# CANBUS.net
KiCad netlist of a schematic drawn in Altium Designer
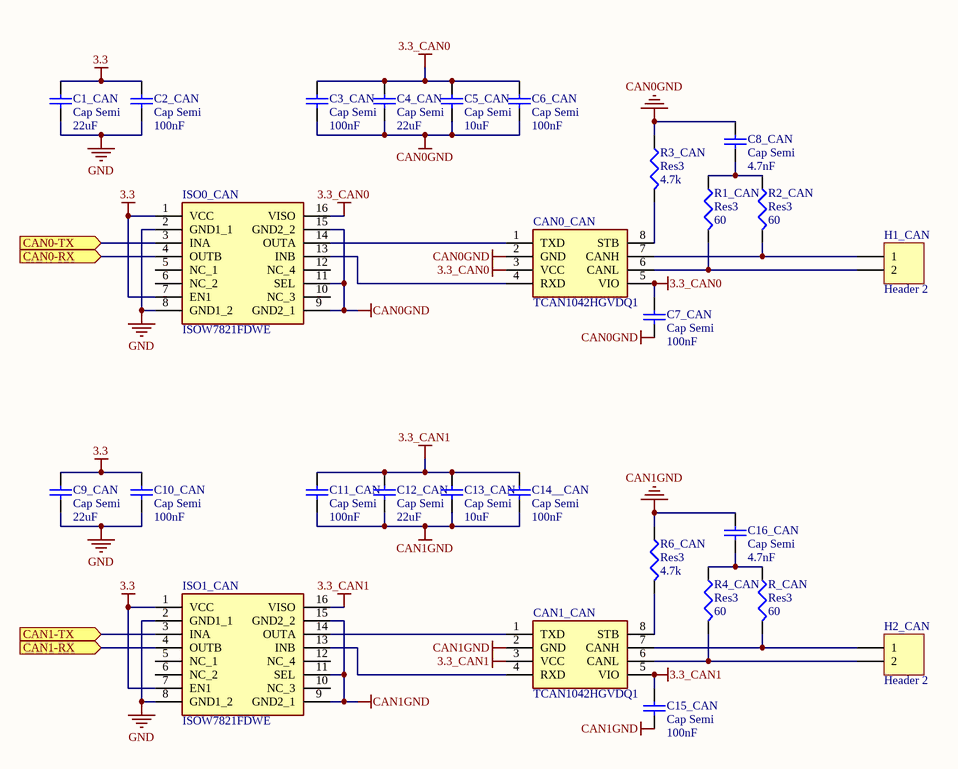
[diagram p0: CANBUS.SchDoc]

(export (version "E")
  (design (tool "Eeschema 10.0.6"))
  (components
    (comp (ref "C1_CAN")
      (value "Cap Semi")
      (footprint "1608[0603]")
      (description "Capacitor (Semiconductor SIM Model)")
      (fields (field (name "ALTIUM_VALUE") "22uF") (field (name "PUBLISHER") "Altium Limited"))
      (libsource (lib "Miscellaneous Devices") (part "Cap Semi"))
    )
    (comp (ref "C2_CAN")
      (value "Cap Semi")
      (footprint "1608[0603]")
      (description "Capacitor (Semiconductor SIM Model)")
      (fields (field (name "ALTIUM_VALUE") "100nF") (field (name "PUBLISHER") "Altium Limited"))
      (libsource (lib "Miscellaneous Devices") (part "Cap Semi"))
    )
    (comp (ref "C3_CAN")
      (value "Cap Semi")
      (footprint "1608[0603]")
      (description "Capacitor (Semiconductor SIM Model)")
      (fields (field (name "ALTIUM_VALUE") "100nF") (field (name "PUBLISHER") "Altium Limited"))
      (libsource (lib "Miscellaneous Devices") (part "Cap Semi"))
    )
    (comp (ref "C4_CAN")
      (value "Cap Semi")
      (footprint "1608[0603]")
      (description "Capacitor (Semiconductor SIM Model)")
      (fields (field (name "ALTIUM_VALUE") "22uF") (field (name "PUBLISHER") "Altium Limited"))
      (libsource (lib "Miscellaneous Devices") (part "Cap Semi"))
    )
    (comp (ref "C5_CAN")
      (value "Cap Semi")
      (footprint "1608[0603]")
      (description "Capacitor (Semiconductor SIM Model)")
      (fields (field (name "ALTIUM_VALUE") "10uF") (field (name "PUBLISHER") "Altium Limited"))
      (libsource (lib "Miscellaneous Devices") (part "Cap Semi"))
    )
    (comp (ref "C6_CAN")
      (value "Cap Semi")
      (footprint "1608[0603]")
      (description "Capacitor (Semiconductor SIM Model)")
      (fields (field (name "ALTIUM_VALUE") "100nF") (field (name "PUBLISHER") "Altium Limited"))
      (libsource (lib "Miscellaneous Devices") (part "Cap Semi"))
    )
    (comp (ref "C7_CAN")
      (value "Cap Semi")
      (footprint "1608[0603]")
      (description "Capacitor (Semiconductor SIM Model)")
      (fields (field (name "ALTIUM_VALUE") "100nF") (field (name "PUBLISHER") "Altium Limited"))
      (libsource (lib "Miscellaneous Devices") (part "Cap Semi"))
    )
    (comp (ref "C8_CAN")
      (value "Cap Semi")
      (footprint "1608[0603]")
      (description "Capacitor (Semiconductor SIM Model)")
      (fields (field (name "ALTIUM_VALUE") "4.7nF") (field (name "PUBLISHER") "Altium Limited"))
      (libsource (lib "Miscellaneous Devices") (part "Cap Semi"))
    )
    (comp (ref "C9_CAN")
      (value "Cap Semi")
      (footprint "1608[0603]")
      (description "Capacitor (Semiconductor SIM Model)")
      (fields (field (name "ALTIUM_VALUE") "22uF") (field (name "PUBLISHER") "Altium Limited"))
      (libsource (lib "Miscellaneous Devices") (part "Cap Semi"))
    )
    (comp (ref "C10_CAN")
      (value "Cap Semi")
      (footprint "1608[0603]")
      (description "Capacitor (Semiconductor SIM Model)")
      (fields (field (name "ALTIUM_VALUE") "100nF") (field (name "PUBLISHER") "Altium Limited"))
      (libsource (lib "Miscellaneous Devices") (part "Cap Semi"))
    )
    (comp (ref "C11_CAN")
      (value "Cap Semi")
      (footprint "1608[0603]")
      (description "Capacitor (Semiconductor SIM Model)")
      (fields (field (name "ALTIUM_VALUE") "100nF") (field (name "PUBLISHER") "Altium Limited"))
      (libsource (lib "Miscellaneous Devices") (part "Cap Semi"))
    )
    (comp (ref "C12_CAN")
      (value "Cap Semi")
      (footprint "1608[0603]")
      (description "Capacitor (Semiconductor SIM Model)")
      (fields (field (name "ALTIUM_VALUE") "22uF") (field (name "PUBLISHER") "Altium Limited"))
      (libsource (lib "Miscellaneous Devices") (part "Cap Semi"))
    )
    (comp (ref "C13_CAN")
      (value "Cap Semi")
      (footprint "1608[0603]")
      (description "Capacitor (Semiconductor SIM Model)")
      (fields (field (name "ALTIUM_VALUE") "10uF") (field (name "PUBLISHER") "Altium Limited"))
      (libsource (lib "Miscellaneous Devices") (part "Cap Semi"))
    )
    (comp (ref "C14__CAN")
      (value "Cap Semi")
      (footprint "1608[0603]")
      (description "Capacitor (Semiconductor SIM Model)")
      (fields (field (name "ALTIUM_VALUE") "100nF") (field (name "PUBLISHER") "Altium Limited"))
      (libsource (lib "Miscellaneous Devices") (part "Cap Semi"))
    )
    (comp (ref "C15_CAN")
      (value "Cap Semi")
      (footprint "1608[0603]")
      (description "Capacitor (Semiconductor SIM Model)")
      (fields (field (name "ALTIUM_VALUE") "100nF") (field (name "PUBLISHER") "Altium Limited"))
      (libsource (lib "Miscellaneous Devices") (part "Cap Semi"))
    )
    (comp (ref "C16_CAN")
      (value "Cap Semi")
      (footprint "1608[0603]")
      (description "Capacitor (Semiconductor SIM Model)")
      (fields (field (name "ALTIUM_VALUE") "4.7nF") (field (name "PUBLISHER") "Altium Limited"))
      (libsource (lib "Miscellaneous Devices") (part "Cap Semi"))
    )
    (comp (ref "CAN0_CAN")
      (value "TCAN1042HGVDQ1")
      (footprint "SOIC127P600X175-8N")
      (description "Integrated Circuit")
      (fields
        (field (name "MOUSER PART NUMBER") "595-TCAN1042HGVDQ1")
        (field (name "RS PART NUMBER") "1330710P")
      )
      (libsource (lib "CANBUS") (part "TCAN1042HGVDQ1"))
    )
    (comp (ref "CAN1_CAN")
      (value "TCAN1042HGVDQ1")
      (footprint "SOIC127P600X175-8N")
      (description "Integrated Circuit")
      (fields
        (field (name "MOUSER PART NUMBER") "595-TCAN1042HGVDQ1")
        (field (name "RS PART NUMBER") "1330710P")
      )
      (libsource (lib "CANBUS") (part "TCAN1042HGVDQ1"))
    )
    (comp (ref "H1_CAN")
      (value "Header 2")
      (footprint "HDR1X2")
      (description "Header, 2-Pin")
      (fields (field (name "PUBLISHER") "Altium Limited"))
      (libsource (lib "Miscellaneous Connectors") (part "Header 2"))
    )
    (comp (ref "H2_CAN")
      (value "Header 2")
      (footprint "HDR1X2")
      (description "Header, 2-Pin")
      (fields (field (name "PUBLISHER") "Altium Limited"))
      (libsource (lib "Miscellaneous Connectors") (part "Header 2"))
    )
    (comp (ref "ISO0_CAN")
      (value "ISOW7821FDWE")
      (footprint "SOIC127P1030X265-16N")
      (description "Integrated Circuit")
      (fields (field (name "MOUSER PART NUMBER") "595-ISOW7821FDWE"))
      (libsource (lib "CANBUS") (part "ISOW7821FDWE"))
    )
    (comp (ref "ISO1_CAN")
      (value "ISOW7821FDWE")
      (footprint "SOIC127P1030X265-16N")
      (description "Integrated Circuit")
      (fields (field (name "MOUSER PART NUMBER") "595-ISOW7821FDWE"))
      (libsource (lib "CANBUS") (part "ISOW7821FDWE"))
    )
    (comp (ref "R1_CAN")
      (value "Res3")
      (footprint "J1-0603")
      (description "Resistor")
      (fields (field (name "ALTIUM_VALUE") "60") (field (name "PUBLISHER") "Altium Limited"))
      (libsource (lib "Miscellaneous Devices") (part "Res3"))
    )
    (comp (ref "R2_CAN")
      (value "Res3")
      (footprint "J1-0603")
      (description "Resistor")
      (fields (field (name "ALTIUM_VALUE") "60") (field (name "PUBLISHER") "Altium Limited"))
      (libsource (lib "Miscellaneous Devices") (part "Res3"))
    )
    (comp (ref "R3_CAN")
      (value "Res3")
      (footprint "J1-0603")
      (description "Resistor")
      (fields (field (name "ALTIUM_VALUE") "4.7k") (field (name "PUBLISHER") "Altium Limited"))
      (libsource (lib "Miscellaneous Devices") (part "Res3"))
    )
    (comp (ref "R4_CAN")
      (value "Res3")
      (footprint "J1-0603")
      (description "Resistor")
      (fields (field (name "ALTIUM_VALUE") "60") (field (name "PUBLISHER") "Altium Limited"))
      (libsource (lib "Miscellaneous Devices") (part "Res3"))
    )
    (comp (ref "R6_CAN")
      (value "Res3")
      (footprint "J1-0603")
      (description "Resistor")
      (fields (field (name "ALTIUM_VALUE") "4.7k") (field (name "PUBLISHER") "Altium Limited"))
      (libsource (lib "Miscellaneous Devices") (part "Res3"))
    )
    (comp (ref "R_CAN")
      (value "Res3")
      (footprint "J1-0603")
      (description "Resistor")
      (fields (field (name "ALTIUM_VALUE") "60") (field (name "PUBLISHER") "Altium Limited"))
      (libsource (lib "Miscellaneous Devices") (part "Res3"))
    )
  )
  (nets
    (net (code "1") (name "/CAN0-RX") (class "Default")
      (node (ref "ISO0_CAN") (pin "4") (pinfunction "OUTB_4") (pintype "passive"))
    )
    (net (code "2") (name "/CAN0-TX") (class "Default")
      (node (ref "ISO0_CAN") (pin "3") (pinfunction "INA_3") (pintype "passive"))
    )
    (net (code "3") (name "/CAN1-RX") (class "Default")
      (node (ref "ISO1_CAN") (pin "4") (pinfunction "OUTB_4") (pintype "passive"))
    )
    (net (code "4") (name "/CAN1-TX") (class "Default")
      (node (ref "ISO1_CAN") (pin "3") (pinfunction "INA_3") (pintype "passive"))
    )
    (net (code "5") (name "3.3") (class "Default")
      (node (ref "C10_CAN") (pin "2") (pinfunction "2_2") (pintype "passive"))
      (node (ref "C1_CAN") (pin "2") (pinfunction "2_2") (pintype "passive"))
      (node (ref "C2_CAN") (pin "2") (pinfunction "2_2") (pintype "passive"))
      (node (ref "C9_CAN") (pin "2") (pinfunction "2_2") (pintype "passive"))
      (node (ref "ISO0_CAN") (pin "1") (pinfunction "VCC_1") (pintype "passive"))
      (node (ref "ISO0_CAN") (pin "7") (pinfunction "EN1_7") (pintype "passive"))
      (node (ref "ISO1_CAN") (pin "1") (pinfunction "VCC_1") (pintype "passive"))
      (node (ref "ISO1_CAN") (pin "7") (pinfunction "EN1_7") (pintype "passive"))
    )
    (net (code "6") (name "3.3_CAN0") (class "Default")
      (node (ref "C3_CAN") (pin "2") (pinfunction "2_2") (pintype "passive"))
      (node (ref "C4_CAN") (pin "2") (pinfunction "2_2") (pintype "passive"))
      (node (ref "C5_CAN") (pin "2") (pinfunction "2_2") (pintype "passive"))
      (node (ref "C6_CAN") (pin "2") (pinfunction "2_2") (pintype "passive"))
      (node (ref "C7_CAN") (pin "2") (pinfunction "2_2") (pintype "passive"))
      (node (ref "CAN0_CAN") (pin "3") (pinfunction "VCC_3") (pintype "power_in"))
      (node (ref "CAN0_CAN") (pin "5") (pinfunction "VIO_5") (pintype "power_in"))
      (node (ref "ISO0_CAN") (pin "16") (pinfunction "VISO_16") (pintype "passive"))
    )
    (net (code "7") (name "3.3_CAN1") (class "Default")
      (node (ref "C11_CAN") (pin "2") (pinfunction "2_2") (pintype "passive"))
      (node (ref "C12_CAN") (pin "2") (pinfunction "2_2") (pintype "passive"))
      (node (ref "C13_CAN") (pin "2") (pinfunction "2_2") (pintype "passive"))
      (node (ref "C14__CAN") (pin "2") (pinfunction "2_2") (pintype "passive"))
      (node (ref "C15_CAN") (pin "2") (pinfunction "2_2") (pintype "passive"))
      (node (ref "CAN1_CAN") (pin "3") (pinfunction "VCC_3") (pintype "power_in"))
      (node (ref "CAN1_CAN") (pin "5") (pinfunction "VIO_5") (pintype "power_in"))
      (node (ref "ISO1_CAN") (pin "16") (pinfunction "VISO_16") (pintype "passive"))
    )
    (net (code "8") (name "CAN0GND") (class "Default")
      (node (ref "C3_CAN") (pin "1") (pinfunction "1_1") (pintype "passive"))
      (node (ref "C4_CAN") (pin "1") (pinfunction "1_1") (pintype "passive"))
      (node (ref "C5_CAN") (pin "1") (pinfunction "1_1") (pintype "passive"))
      (node (ref "C6_CAN") (pin "1") (pinfunction "1_1") (pintype "passive"))
      (node (ref "C7_CAN") (pin "1") (pinfunction "1_1") (pintype "passive"))
      (node (ref "C8_CAN") (pin "2") (pinfunction "2_2") (pintype "passive"))
      (node (ref "CAN0_CAN") (pin "2") (pinfunction "GND_2") (pintype "power_in"))
      (node (ref "ISO0_CAN") (pin "11") (pinfunction "SEL_11") (pintype "passive"))
      (node (ref "ISO0_CAN") (pin "15") (pinfunction "GND2_2_15") (pintype "passive"))
      (node (ref "ISO0_CAN") (pin "9") (pinfunction "GND2_1_9") (pintype "passive"))
      (node (ref "R3_CAN") (pin "1") (pinfunction "1_1") (pintype "passive"))
    )
    (net (code "9") (name "CAN1GND") (class "Default")
      (node (ref "C11_CAN") (pin "1") (pinfunction "1_1") (pintype "passive"))
      (node (ref "C12_CAN") (pin "1") (pinfunction "1_1") (pintype "passive"))
      (node (ref "C13_CAN") (pin "1") (pinfunction "1_1") (pintype "passive"))
      (node (ref "C14__CAN") (pin "1") (pinfunction "1_1") (pintype "passive"))
      (node (ref "C15_CAN") (pin "1") (pinfunction "1_1") (pintype "passive"))
      (node (ref "C16_CAN") (pin "2") (pinfunction "2_2") (pintype "passive"))
      (node (ref "CAN1_CAN") (pin "2") (pinfunction "GND_2") (pintype "power_in"))
      (node (ref "ISO1_CAN") (pin "11") (pinfunction "SEL_11") (pintype "passive"))
      (node (ref "ISO1_CAN") (pin "15") (pinfunction "GND2_2_15") (pintype "passive"))
      (node (ref "ISO1_CAN") (pin "9") (pinfunction "GND2_1_9") (pintype "passive"))
      (node (ref "R6_CAN") (pin "1") (pinfunction "1_1") (pintype "passive"))
    )
    (net (code "10") (name "GND") (class "Default")
      (node (ref "C10_CAN") (pin "1") (pinfunction "1_1") (pintype "passive"))
      (node (ref "C1_CAN") (pin "1") (pinfunction "1_1") (pintype "passive"))
      (node (ref "C2_CAN") (pin "1") (pinfunction "1_1") (pintype "passive"))
      (node (ref "C9_CAN") (pin "1") (pinfunction "1_1") (pintype "passive"))
      (node (ref "ISO0_CAN") (pin "2") (pinfunction "GND1_1_2") (pintype "passive"))
      (node (ref "ISO0_CAN") (pin "8") (pinfunction "GND1_2_8") (pintype "passive"))
      (node (ref "ISO1_CAN") (pin "2") (pinfunction "GND1_1_2") (pintype "passive"))
      (node (ref "ISO1_CAN") (pin "8") (pinfunction "GND1_2_8") (pintype "passive"))
    )
    (net (code "11") (name "Net-(C8_CAN-Pad1)") (class "Default")
      (node (ref "C8_CAN") (pin "1") (pinfunction "1_1") (pintype "passive"))
      (node (ref "R1_CAN") (pin "1") (pinfunction "1_1") (pintype "passive"))
      (node (ref "R2_CAN") (pin "1") (pinfunction "1_1") (pintype "passive"))
    )
    (net (code "12") (name "Net-(C16_CAN-Pad1)") (class "Default")
      (node (ref "C16_CAN") (pin "1") (pinfunction "1_1") (pintype "passive"))
      (node (ref "R4_CAN") (pin "1") (pinfunction "1_1") (pintype "passive"))
      (node (ref "R_CAN") (pin "1") (pinfunction "1_1") (pintype "passive"))
    )
    (net (code "13") (name "Net-(CAN0_CAN-CANH)") (class "Default")
      (node (ref "CAN0_CAN") (pin "7") (pinfunction "CANH_7") (pintype "passive"))
      (node (ref "H1_CAN") (pin "1") (pinfunction "1_1") (pintype "passive"))
      (node (ref "R2_CAN") (pin "2") (pinfunction "2_2") (pintype "passive"))
    )
    (net (code "14") (name "Net-(CAN0_CAN-CANL)") (class "Default")
      (node (ref "CAN0_CAN") (pin "6") (pinfunction "CANL_6") (pintype "passive"))
      (node (ref "H1_CAN") (pin "2") (pinfunction "2_2") (pintype "passive"))
      (node (ref "R1_CAN") (pin "2") (pinfunction "2_2") (pintype "passive"))
    )
    (net (code "15") (name "Net-(CAN0_CAN-RXD)") (class "Default")
      (node (ref "CAN0_CAN") (pin "4") (pinfunction "RXD_4") (pintype "passive"))
      (node (ref "ISO0_CAN") (pin "13") (pinfunction "INB_13") (pintype "passive"))
    )
    (net (code "16") (name "Net-(CAN0_CAN-STB)") (class "Default")
      (node (ref "CAN0_CAN") (pin "8") (pinfunction "STB_8") (pintype "passive"))
      (node (ref "R3_CAN") (pin "2") (pinfunction "2_2") (pintype "passive"))
    )
    (net (code "17") (name "Net-(CAN0_CAN-TXD)") (class "Default")
      (node (ref "CAN0_CAN") (pin "1") (pinfunction "TXD_1") (pintype "passive"))
      (node (ref "ISO0_CAN") (pin "14") (pinfunction "OUTA_14") (pintype "passive"))
    )
    (net (code "18") (name "Net-(CAN1_CAN-CANH)") (class "Default")
      (node (ref "CAN1_CAN") (pin "7") (pinfunction "CANH_7") (pintype "passive"))
      (node (ref "H2_CAN") (pin "1") (pinfunction "1_1") (pintype "passive"))
      (node (ref "R_CAN") (pin "2") (pinfunction "2_2") (pintype "passive"))
    )
    (net (code "19") (name "Net-(CAN1_CAN-CANL)") (class "Default")
      (node (ref "CAN1_CAN") (pin "6") (pinfunction "CANL_6") (pintype "passive"))
      (node (ref "H2_CAN") (pin "2") (pinfunction "2_2") (pintype "passive"))
      (node (ref "R4_CAN") (pin "2") (pinfunction "2_2") (pintype "passive"))
    )
    (net (code "20") (name "Net-(CAN1_CAN-RXD)") (class "Default")
      (node (ref "CAN1_CAN") (pin "4") (pinfunction "RXD_4") (pintype "passive"))
      (node (ref "ISO1_CAN") (pin "13") (pinfunction "INB_13") (pintype "passive"))
    )
    (net (code "21") (name "Net-(CAN1_CAN-STB)") (class "Default")
      (node (ref "CAN1_CAN") (pin "8") (pinfunction "STB_8") (pintype "passive"))
      (node (ref "R6_CAN") (pin "2") (pinfunction "2_2") (pintype "passive"))
    )
    (net (code "22") (name "Net-(CAN1_CAN-TXD)") (class "Default")
      (node (ref "CAN1_CAN") (pin "1") (pinfunction "TXD_1") (pintype "passive"))
      (node (ref "ISO1_CAN") (pin "14") (pinfunction "OUTA_14") (pintype "passive"))
    )
    (net (code "23") (name "unconnected-(ISO0_CAN-NC_1-Pad5)") (class "Default")
      (node (ref "ISO0_CAN") (pin "5") (pinfunction "NC_1_5") (pintype "passive"))
    )
    (net (code "24") (name "unconnected-(ISO0_CAN-NC_2-Pad6)") (class "Default")
      (node (ref "ISO0_CAN") (pin "6") (pinfunction "NC_2_6") (pintype "passive"))
    )
    (net (code "25") (name "unconnected-(ISO0_CAN-NC_3-Pad10)") (class "Default")
      (node (ref "ISO0_CAN") (pin "10") (pinfunction "NC_3_10") (pintype "passive"))
    )
    (net (code "26") (name "unconnected-(ISO0_CAN-NC_4-Pad12)") (class "Default")
      (node (ref "ISO0_CAN") (pin "12") (pinfunction "NC_4_12") (pintype "passive"))
    )
    (net (code "27") (name "unconnected-(ISO1_CAN-NC_1-Pad5)") (class "Default")
      (node (ref "ISO1_CAN") (pin "5") (pinfunction "NC_1_5") (pintype "passive"))
    )
    (net (code "28") (name "unconnected-(ISO1_CAN-NC_2-Pad6)") (class "Default")
      (node (ref "ISO1_CAN") (pin "6") (pinfunction "NC_2_6") (pintype "passive"))
    )
    (net (code "29") (name "unconnected-(ISO1_CAN-NC_3-Pad10)") (class "Default")
      (node (ref "ISO1_CAN") (pin "10") (pinfunction "NC_3_10") (pintype "passive"))
    )
    (net (code "30") (name "unconnected-(ISO1_CAN-NC_4-Pad12)") (class "Default")
      (node (ref "ISO1_CAN") (pin "12") (pinfunction "NC_4_12") (pintype "passive"))
    )
  )
)
